# SCH_MS5803_Adapter_FFC_2023-08-02.net
KiCad netlist of a schematic drawn in EasyEDA
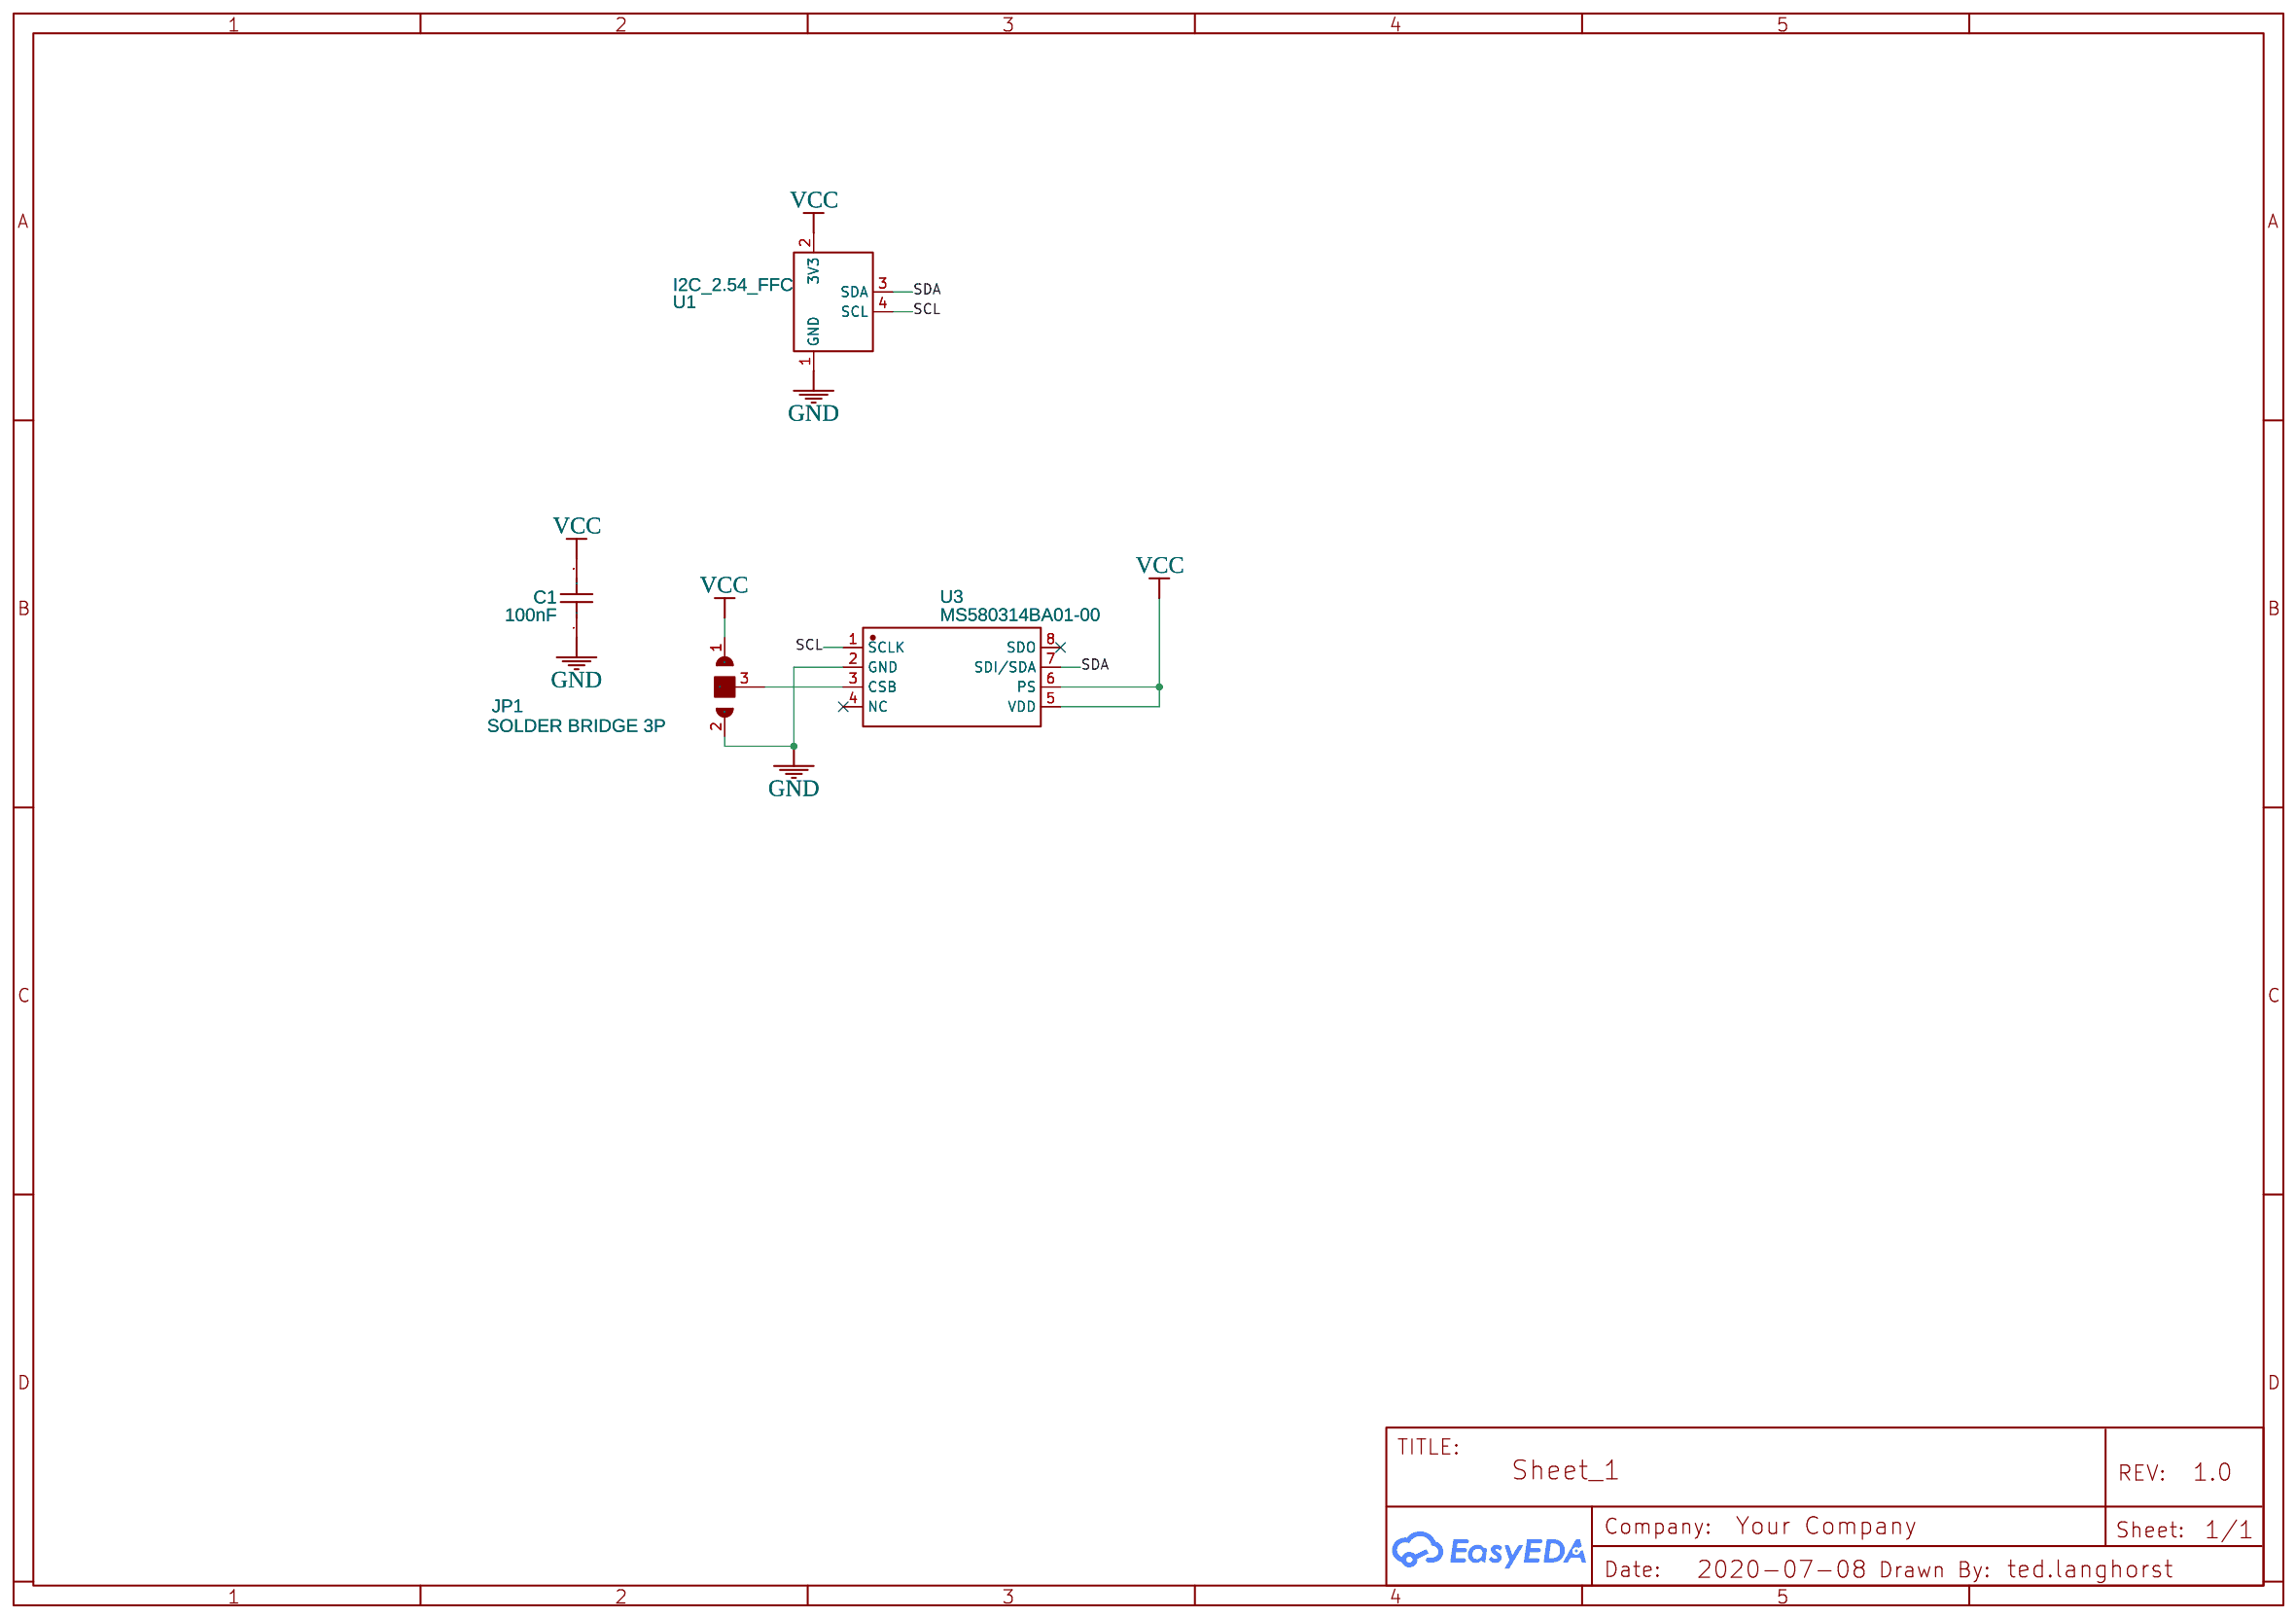
[diagram p0: schematic sheet]

(export (version "E")
  (design (tool "Eeschema 10.0.6"))
  (components
    (comp (ref "C1")
      (value "100nF")
      (fields
        (field (name "Manufacturer Part") "CC0603KRX7R9BB104")
        (field (name "Manufacturer") "YAGEO(国巨)")
      )
      (libsource (lib "") (part "CC0603KRX7R9BB104"))
    )
    (comp (ref "JP1") (value "SOLDER BRIDGE 3P") (libsource (lib "") (part "SOLDER BRIDGE")))
    (comp (ref "U1")
      (value "I2C_2.54_FFC")
      (fields
        (field (name "Manufacturer Part") "5-1474644-0")
        (field (name "Manufacturer") "TE Connectivity AMP Connectors")
      )
      (libsource (lib "") (part "I2C_2.54_FFC"))
    )
    (comp (ref "U3") (value "MS580314BA01-00") (libsource (lib "") (part "MS580314BA01-00")))
  )
  (nets
    (net (code "1") (name "/SCL") (class "Default")
      (node (ref "U1") (pin "4") (pinfunction "SCL_4") (pintype "unspecified"))
      (node (ref "U3") (pin "1") (pinfunction "SCLK_1") (pintype "unspecified"))
    )
    (net (code "2") (name "/SDA") (class "Default")
      (node (ref "U1") (pin "3") (pinfunction "SDA_3") (pintype "unspecified"))
      (node (ref "U3") (pin "7") (pinfunction "SDI/SDA_7") (pintype "unspecified"))
    )
    (net (code "3") (name "GND") (class "Default")
      (node (ref "C1") (pin "1") (pinfunction "1_1") (pintype "unspecified"))
      (node (ref "JP1") (pin "2") (pinfunction "2_2") (pintype "unspecified"))
      (node (ref "U1") (pin "1") (pinfunction "GND_1") (pintype "unspecified"))
      (node (ref "U3") (pin "2") (pinfunction "GND_2") (pintype "unspecified"))
    )
    (net (code "4") (name "Net-(U3-CSB)") (class "Default")
      (node (ref "JP1") (pin "3") (pinfunction "3_3") (pintype "unspecified"))
      (node (ref "U3") (pin "3") (pinfunction "CSB_3") (pintype "unspecified"))
    )
    (net (code "5") (name "VCC") (class "Default")
      (node (ref "C1") (pin "2") (pinfunction "2_2") (pintype "unspecified"))
      (node (ref "JP1") (pin "1") (pinfunction "1_1") (pintype "unspecified"))
      (node (ref "U1") (pin "2") (pinfunction "3V3_2") (pintype "unspecified"))
      (node (ref "U3") (pin "5") (pinfunction "VDD_5") (pintype "unspecified"))
      (node (ref "U3") (pin "6") (pinfunction "PS_6") (pintype "unspecified"))
    )
    (net (code "6") (name "unconnected-(U3-NC-Pad4)") (class "Default")
      (node (ref "U3") (pin "4") (pinfunction "NC_4") (pintype "unspecified+no_connect"))
    )
    (net (code "7") (name "unconnected-(U3-SDO-Pad8)") (class "Default")
      (node (ref "U3") (pin "8") (pinfunction "SDO_8") (pintype "unspecified+no_connect"))
    )
  )
)
